# 2_Battery_indicator.net
KiCad netlist of a schematic drawn in Altium Designer
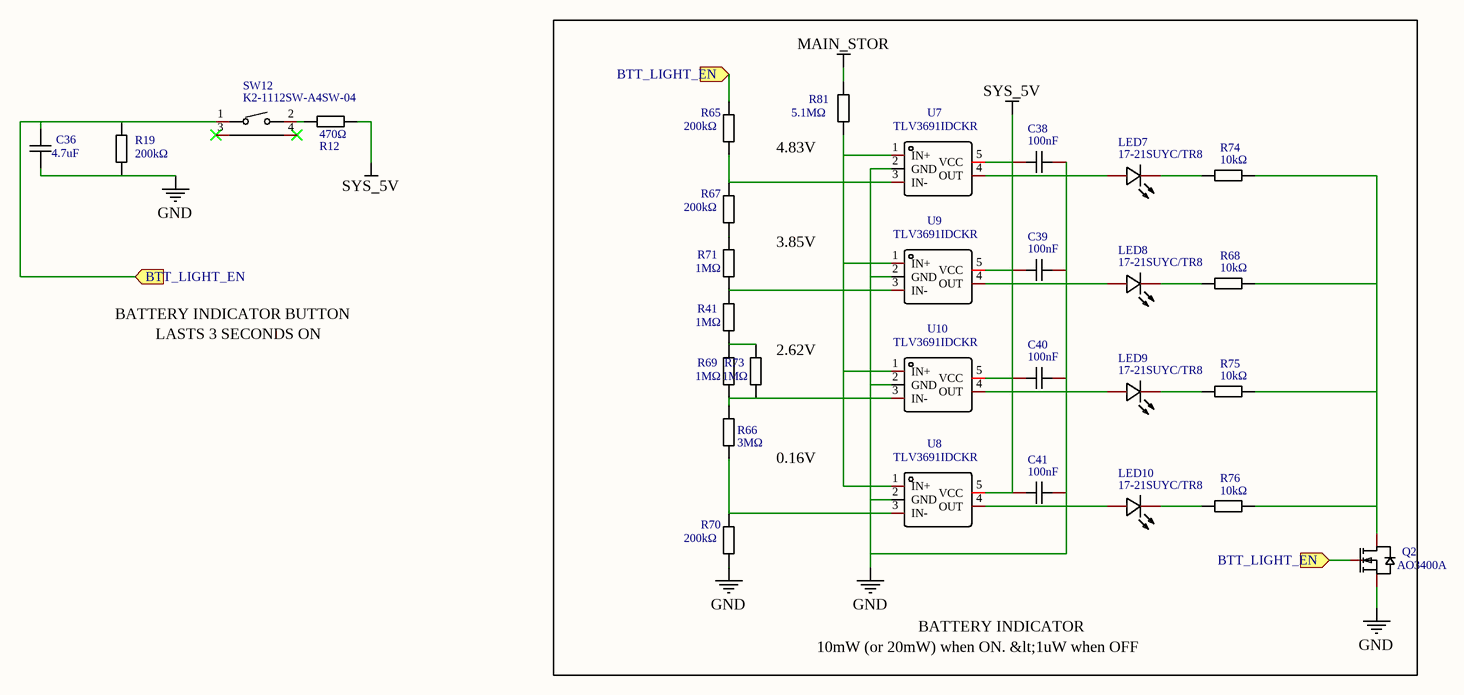
[diagram p0: 2_Battery indicator.schdoc]

(export (version "E")
  (design (tool "Eeschema 10.0.6"))
  (components
    (comp (ref "C36")
      (value "4.7uF")
      (fields
        (field (name "NAME") "4.7uF")
        (field (name "MANUFACTURER PART") "CL10A475KO8NNNC")
        (field (name "MANUFACTURER") "SAMSUNG")
      )
      (libsource (lib "altium-import") (part "root_1_CL10A475KO8NNNC_"))
    )
    (comp (ref "C38")
      (value "100nF")
      (fields
        (field (name "NAME") "100nF")
        (field (name "MANUFACTURER") "YAGEO")
        (field (name "MANUFACTURER PART") "CC0603KRX7R9BB104")
      )
      (libsource (lib "altium-import") (part "root_0_CC0603KRX7R9BB104_"))
    )
    (comp (ref "C39")
      (value "100nF")
      (fields
        (field (name "NAME") "100nF")
        (field (name "MANUFACTURER") "YAGEO")
        (field (name "MANUFACTURER PART") "CC0603KRX7R9BB104")
      )
      (libsource (lib "altium-import") (part "root_0_CC0603KRX7R9BB104_"))
    )
    (comp (ref "C40")
      (value "100nF")
      (fields
        (field (name "NAME") "100nF")
        (field (name "MANUFACTURER") "YAGEO")
        (field (name "MANUFACTURER PART") "CC0603KRX7R9BB104")
      )
      (libsource (lib "altium-import") (part "root_0_CC0603KRX7R9BB104_"))
    )
    (comp (ref "C41")
      (value "100nF")
      (fields
        (field (name "NAME") "100nF")
        (field (name "MANUFACTURER") "YAGEO")
        (field (name "MANUFACTURER PART") "CC0603KRX7R9BB104")
      )
      (libsource (lib "altium-import") (part "root_0_CC0603KRX7R9BB104_"))
    )
    (comp (ref "LED7")
      (value "17-21SUYC/TR8")
      (fields (field (name "NAME") "17-21SUYC/TR8") (field (name "MANUFACTURER") "KENTO"))
      (libsource (lib "altium-import") (part "root_2_17-21SUYC/TR8_"))
    )
    (comp (ref "LED8")
      (value "17-21SUYC/TR8")
      (fields (field (name "NAME") "17-21SUYC/TR8") (field (name "MANUFACTURER") "KENTO"))
      (libsource (lib "altium-import") (part "root_2_17-21SUYC/TR8_"))
    )
    (comp (ref "LED9")
      (value "17-21SUYC/TR8")
      (fields (field (name "NAME") "17-21SUYC/TR8") (field (name "MANUFACTURER") "KENTO"))
      (libsource (lib "altium-import") (part "root_2_17-21SUYC/TR8_"))
    )
    (comp (ref "LED10")
      (value "17-21SUYC/TR8")
      (fields (field (name "NAME") "17-21SUYC/TR8") (field (name "MANUFACTURER") "KENTO"))
      (libsource (lib "altium-import") (part "root_2_17-21SUYC/TR8_"))
    )
    (comp (ref "Q2")
      (value "AO3400A")
      (fields (field (name "NAME") "AO3400A") (field (name "MANUFACTURER") "HUASHUO(华朔)"))
      (libsource (lib "altium-import") (part "root_0_AO3400A_"))
    )
    (comp (ref "R12")
      (value "470Ω")
      (fields
        (field (name "NAME") "470Ω")
        (field (name "MANUFACTURER") "UniOhm")
        (field (name "MANUFACTURER PART") "0603WAF4700T5E")
      )
      (libsource (lib "altium-import") (part "root_0_0603WAF4700T5E_"))
    )
    (comp (ref "R19")
      (value "200kΩ")
      (fields
        (field (name "NAME") "200kΩ")
        (field (name "MANUFACTURER") "UniOhm")
        (field (name "MANUFACTURER PART") "0603WAF2003T5E")
      )
      (libsource (lib "altium-import") (part "root_3_0603WAF2003T5E_"))
    )
    (comp (ref "R41")
      (value "1MΩ")
      (fields
        (field (name "NAME") "1MΩ")
        (field (name "MANUFACTURER") "UniOhm")
        (field (name "MANUFACTURER PART") "0603WAF1004T5E")
      )
      (libsource (lib "altium-import") (part "root_1_0603WAF1004T5E_"))
    )
    (comp (ref "R65")
      (value "200kΩ")
      (fields
        (field (name "NAME") "200kΩ")
        (field (name "MANUFACTURER") "UniOhm")
        (field (name "MANUFACTURER PART") "0603WAF2003T5E")
      )
      (libsource (lib "altium-import") (part "root_1_0603WAF2003T5E_"))
    )
    (comp (ref "R66")
      (value "3MΩ")
      (fields
        (field (name "NAME") "3MΩ")
        (field (name "MANUFACTURER") "UniOhm")
        (field (name "MANUFACTURER PART") "0603WAF3004T5E")
      )
      (libsource (lib "altium-import") (part "root_1_0603WAF3004T5E_"))
    )
    (comp (ref "R67")
      (value "200kΩ")
      (fields
        (field (name "NAME") "200kΩ")
        (field (name "MANUFACTURER") "UniOhm")
        (field (name "MANUFACTURER PART") "0603WAF2003T5E")
      )
      (libsource (lib "altium-import") (part "root_1_0603WAF2003T5E_"))
    )
    (comp (ref "R68")
      (value "10kΩ")
      (fields
        (field (name "NAME") "10kΩ")
        (field (name "MANUFACTURER") "UniOhm")
        (field (name "MANUFACTURER PART") "0603WAF1002T5E")
      )
      (libsource (lib "altium-import") (part "root_0_0603WAF1002T5E_"))
    )
    (comp (ref "R69")
      (value "1MΩ")
      (fields
        (field (name "NAME") "1MΩ")
        (field (name "MANUFACTURER") "UniOhm")
        (field (name "MANUFACTURER PART") "0603WAF1004T5E")
      )
      (libsource (lib "altium-import") (part "root_1_0603WAF1004T5E_"))
    )
    (comp (ref "R70")
      (value "200kΩ")
      (fields
        (field (name "NAME") "200kΩ")
        (field (name "MANUFACTURER") "UniOhm")
        (field (name "MANUFACTURER PART") "0603WAF2003T5E")
      )
      (libsource (lib "altium-import") (part "root_1_0603WAF2003T5E_"))
    )
    (comp (ref "R71")
      (value "1MΩ")
      (fields
        (field (name "NAME") "1MΩ")
        (field (name "MANUFACTURER") "UniOhm")
        (field (name "MANUFACTURER PART") "0603WAF1004T5E")
      )
      (libsource (lib "altium-import") (part "root_1_0603WAF1004T5E_"))
    )
    (comp (ref "R73")
      (value "1MΩ")
      (fields
        (field (name "NAME") "1MΩ")
        (field (name "MANUFACTURER") "UniOhm")
        (field (name "MANUFACTURER PART") "0603WAF1004T5E")
      )
      (libsource (lib "altium-import") (part "root_1_0603WAF1004T5E_"))
    )
    (comp (ref "R74")
      (value "10kΩ")
      (fields
        (field (name "NAME") "10kΩ")
        (field (name "MANUFACTURER") "UniOhm")
        (field (name "MANUFACTURER PART") "0603WAF1002T5E")
      )
      (libsource (lib "altium-import") (part "root_0_0603WAF1002T5E_"))
    )
    (comp (ref "R75")
      (value "10kΩ")
      (fields
        (field (name "NAME") "10kΩ")
        (field (name "MANUFACTURER") "UniOhm")
        (field (name "MANUFACTURER PART") "0603WAF1002T5E")
      )
      (libsource (lib "altium-import") (part "root_0_0603WAF1002T5E_"))
    )
    (comp (ref "R76")
      (value "10kΩ")
      (fields
        (field (name "NAME") "10kΩ")
        (field (name "MANUFACTURER") "UniOhm")
        (field (name "MANUFACTURER PART") "0603WAF1002T5E")
      )
      (libsource (lib "altium-import") (part "root_0_0603WAF1002T5E_"))
    )
    (comp (ref "R81")
      (value "5.1MΩ")
      (fields
        (field (name "NAME") "5.1MΩ")
        (field (name "MANUFACTURER") "UniOhm")
        (field (name "MANUFACTURER PART") "0603WAF5104T5E")
      )
      (libsource (lib "altium-import") (part "root_1_0603WAF5104T5E_"))
    )
    (comp (ref "SW12")
      (value "K2-1112SW-A4SW-04")
      (fields (field (name "NAME") "K2-1112SW-A4SW-04") (field (name "MANUFACTURER") "Korean Hroparts Elec"))
      (libsource (lib "altium-import") (part "root_0_K2-1112SW-A4SW-04_"))
    )
    (comp (ref "U7")
      (value "TLV3691IDCKR")
      (fields (field (name "NAME") "TLV3691IDCKR") (field (name "MANUFACTURER") "TI(德州仪器)"))
      (libsource (lib "altium-import") (part "root_0_TLV3691IDCKR_"))
    )
    (comp (ref "U8")
      (value "TLV3691IDCKR")
      (fields (field (name "NAME") "TLV3691IDCKR") (field (name "MANUFACTURER") "TI(德州仪器)"))
      (libsource (lib "altium-import") (part "root_0_TLV3691IDCKR_"))
    )
    (comp (ref "U9")
      (value "TLV3691IDCKR")
      (fields (field (name "NAME") "TLV3691IDCKR") (field (name "MANUFACTURER") "TI(德州仪器)"))
      (libsource (lib "altium-import") (part "root_0_TLV3691IDCKR_"))
    )
    (comp (ref "U10")
      (value "TLV3691IDCKR")
      (fields (field (name "NAME") "TLV3691IDCKR") (field (name "MANUFACTURER") "TI(德州仪器)"))
      (libsource (lib "altium-import") (part "root_0_TLV3691IDCKR_"))
    )
  )
  (nets
    (net (code "1") (name "/BTT_LIGHT_EN") (class "Default")
      (node (ref "C36") (pin "2") (pinfunction "2_2") (pintype "passive"))
      (node (ref "Q2") (pin "1") (pinfunction "G_1") (pintype "passive"))
      (node (ref "R19") (pin "1") (pinfunction "1_1") (pintype "passive"))
      (node (ref "R65") (pin "2") (pinfunction "2_2") (pintype "passive"))
      (node (ref "SW12") (pin "1") (pinfunction "1_1") (pintype "passive"))
    )
    (net (code "2") (name "GND") (class "Default")
      (node (ref "C36") (pin "1") (pinfunction "1_1") (pintype "passive"))
      (node (ref "C38") (pin "2") (pinfunction "2_2") (pintype "passive"))
      (node (ref "C39") (pin "2") (pinfunction "2_2") (pintype "passive"))
      (node (ref "C40") (pin "2") (pinfunction "2_2") (pintype "passive"))
      (node (ref "C41") (pin "2") (pinfunction "2_2") (pintype "passive"))
      (node (ref "Q2") (pin "2") (pinfunction "S_2") (pintype "passive"))
      (node (ref "R19") (pin "2") (pinfunction "2_2") (pintype "passive"))
      (node (ref "R70") (pin "1") (pinfunction "1_1") (pintype "passive"))
      (node (ref "U10") (pin "2") (pinfunction "GND_2") (pintype "passive"))
      (node (ref "U7") (pin "2") (pinfunction "GND_2") (pintype "passive"))
      (node (ref "U8") (pin "2") (pinfunction "GND_2") (pintype "passive"))
      (node (ref "U9") (pin "2") (pinfunction "GND_2") (pintype "passive"))
    )
    (net (code "3") (name "MAIN_STOR") (class "Default")
      (node (ref "R81") (pin "1") (pinfunction "1_1") (pintype "passive"))
    )
    (net (code "4") (name "Net-(LED7-+)") (class "Default")
      (node (ref "LED7") (pin "2") (pinfunction "+_2") (pintype "passive"))
      (node (ref "U7") (pin "4") (pinfunction "OUT_4") (pintype "passive"))
    )
    (net (code "5") (name "Net-(LED7--)") (class "Default")
      (node (ref "LED7") (pin "1") (pinfunction "-_1") (pintype "passive"))
      (node (ref "R74") (pin "1") (pinfunction "1_1") (pintype "passive"))
    )
    (net (code "6") (name "Net-(LED8-+)") (class "Default")
      (node (ref "LED8") (pin "2") (pinfunction "+_2") (pintype "passive"))
      (node (ref "U9") (pin "4") (pinfunction "OUT_4") (pintype "passive"))
    )
    (net (code "7") (name "Net-(LED8--)") (class "Default")
      (node (ref "LED8") (pin "1") (pinfunction "-_1") (pintype "passive"))
      (node (ref "R68") (pin "1") (pinfunction "1_1") (pintype "passive"))
    )
    (net (code "8") (name "Net-(LED9-+)") (class "Default")
      (node (ref "LED9") (pin "2") (pinfunction "+_2") (pintype "passive"))
      (node (ref "U10") (pin "4") (pinfunction "OUT_4") (pintype "passive"))
    )
    (net (code "9") (name "Net-(LED9--)") (class "Default")
      (node (ref "LED9") (pin "1") (pinfunction "-_1") (pintype "passive"))
      (node (ref "R75") (pin "1") (pinfunction "1_1") (pintype "passive"))
    )
    (net (code "10") (name "Net-(LED10-+)") (class "Default")
      (node (ref "LED10") (pin "2") (pinfunction "+_2") (pintype "passive"))
      (node (ref "U8") (pin "4") (pinfunction "OUT_4") (pintype "passive"))
    )
    (net (code "11") (name "Net-(LED10--)") (class "Default")
      (node (ref "LED10") (pin "1") (pinfunction "-_1") (pintype "passive"))
      (node (ref "R76") (pin "1") (pinfunction "1_1") (pintype "passive"))
    )
    (net (code "12") (name "Net-(Q2-D)") (class "Default")
      (node (ref "Q2") (pin "3") (pinfunction "D_3") (pintype "passive"))
      (node (ref "R68") (pin "2") (pinfunction "2_2") (pintype "passive"))
      (node (ref "R74") (pin "2") (pinfunction "2_2") (pintype "passive"))
      (node (ref "R75") (pin "2") (pinfunction "2_2") (pintype "passive"))
      (node (ref "R76") (pin "2") (pinfunction "2_2") (pintype "passive"))
    )
    (net (code "13") (name "Net-(R12-Pad1)") (class "Default")
      (node (ref "R12") (pin "1") (pinfunction "1_1") (pintype "passive"))
      (node (ref "SW12") (pin "2") (pinfunction "2_2") (pintype "passive"))
    )
    (net (code "14") (name "Net-(R41-Pad1)") (class "Default")
      (node (ref "R41") (pin "1") (pinfunction "1_1") (pintype "passive"))
      (node (ref "R69") (pin "2") (pinfunction "2_2") (pintype "passive"))
      (node (ref "R73") (pin "2") (pinfunction "2_2") (pintype "passive"))
    )
    (net (code "15") (name "Net-(R67-Pad1)") (class "Default")
      (node (ref "R67") (pin "1") (pinfunction "1_1") (pintype "passive"))
      (node (ref "R71") (pin "2") (pinfunction "2_2") (pintype "passive"))
    )
    (net (code "16") (name "Net-(U7-IN-)") (class "Default")
      (node (ref "R65") (pin "1") (pinfunction "1_1") (pintype "passive"))
      (node (ref "R67") (pin "2") (pinfunction "2_2") (pintype "passive"))
      (node (ref "U7") (pin "3") (pinfunction "IN-_3") (pintype "passive"))
    )
    (net (code "17") (name "Net-(U8-IN-)") (class "Default")
      (node (ref "R66") (pin "1") (pinfunction "1_1") (pintype "passive"))
      (node (ref "R70") (pin "2") (pinfunction "2_2") (pintype "passive"))
      (node (ref "U8") (pin "3") (pinfunction "IN-_3") (pintype "passive"))
    )
    (net (code "18") (name "Net-(U9-IN-)") (class "Default")
      (node (ref "R41") (pin "2") (pinfunction "2_2") (pintype "passive"))
      (node (ref "R71") (pin "1") (pinfunction "1_1") (pintype "passive"))
      (node (ref "U9") (pin "3") (pinfunction "IN-_3") (pintype "passive"))
    )
    (net (code "19") (name "Net-(U10-IN+)") (class "Default")
      (node (ref "R81") (pin "2") (pinfunction "2_2") (pintype "passive"))
      (node (ref "U10") (pin "1") (pinfunction "IN+_1") (pintype "passive"))
      (node (ref "U7") (pin "1") (pinfunction "IN+_1") (pintype "passive"))
      (node (ref "U8") (pin "1") (pinfunction "IN+_1") (pintype "passive"))
      (node (ref "U9") (pin "1") (pinfunction "IN+_1") (pintype "passive"))
    )
    (net (code "20") (name "Net-(U10-IN-)") (class "Default")
      (node (ref "R66") (pin "2") (pinfunction "2_2") (pintype "passive"))
      (node (ref "R69") (pin "1") (pinfunction "1_1") (pintype "passive"))
      (node (ref "R73") (pin "1") (pinfunction "1_1") (pintype "passive"))
      (node (ref "U10") (pin "3") (pinfunction "IN-_3") (pintype "passive"))
    )
    (net (code "21") (name "SYS_5V") (class "Default")
      (node (ref "C38") (pin "1") (pinfunction "1_1") (pintype "passive"))
      (node (ref "C39") (pin "1") (pinfunction "1_1") (pintype "passive"))
      (node (ref "C40") (pin "1") (pinfunction "1_1") (pintype "passive"))
      (node (ref "C41") (pin "1") (pinfunction "1_1") (pintype "passive"))
      (node (ref "R12") (pin "2") (pinfunction "2_2") (pintype "passive"))
      (node (ref "U10") (pin "5") (pinfunction "VCC_5") (pintype "passive"))
      (node (ref "U7") (pin "5") (pinfunction "VCC_5") (pintype "passive"))
      (node (ref "U8") (pin "5") (pinfunction "VCC_5") (pintype "passive"))
      (node (ref "U9") (pin "5") (pinfunction "VCC_5") (pintype "passive"))
    )
    (net (code "22") (name "unconnected-(SW12-Pad3)") (class "Default")
      (node (ref "SW12") (pin "3") (pinfunction "3_3") (pintype "passive+no_connect"))
    )
    (net (code "23") (name "unconnected-(SW12-Pad4)") (class "Default")
      (node (ref "SW12") (pin "4") (pinfunction "4_4") (pintype "passive+no_connect"))
    )
  )
)
